# ESQUEMATICO.net
KiCad netlist of a schematic drawn in EasyEDA
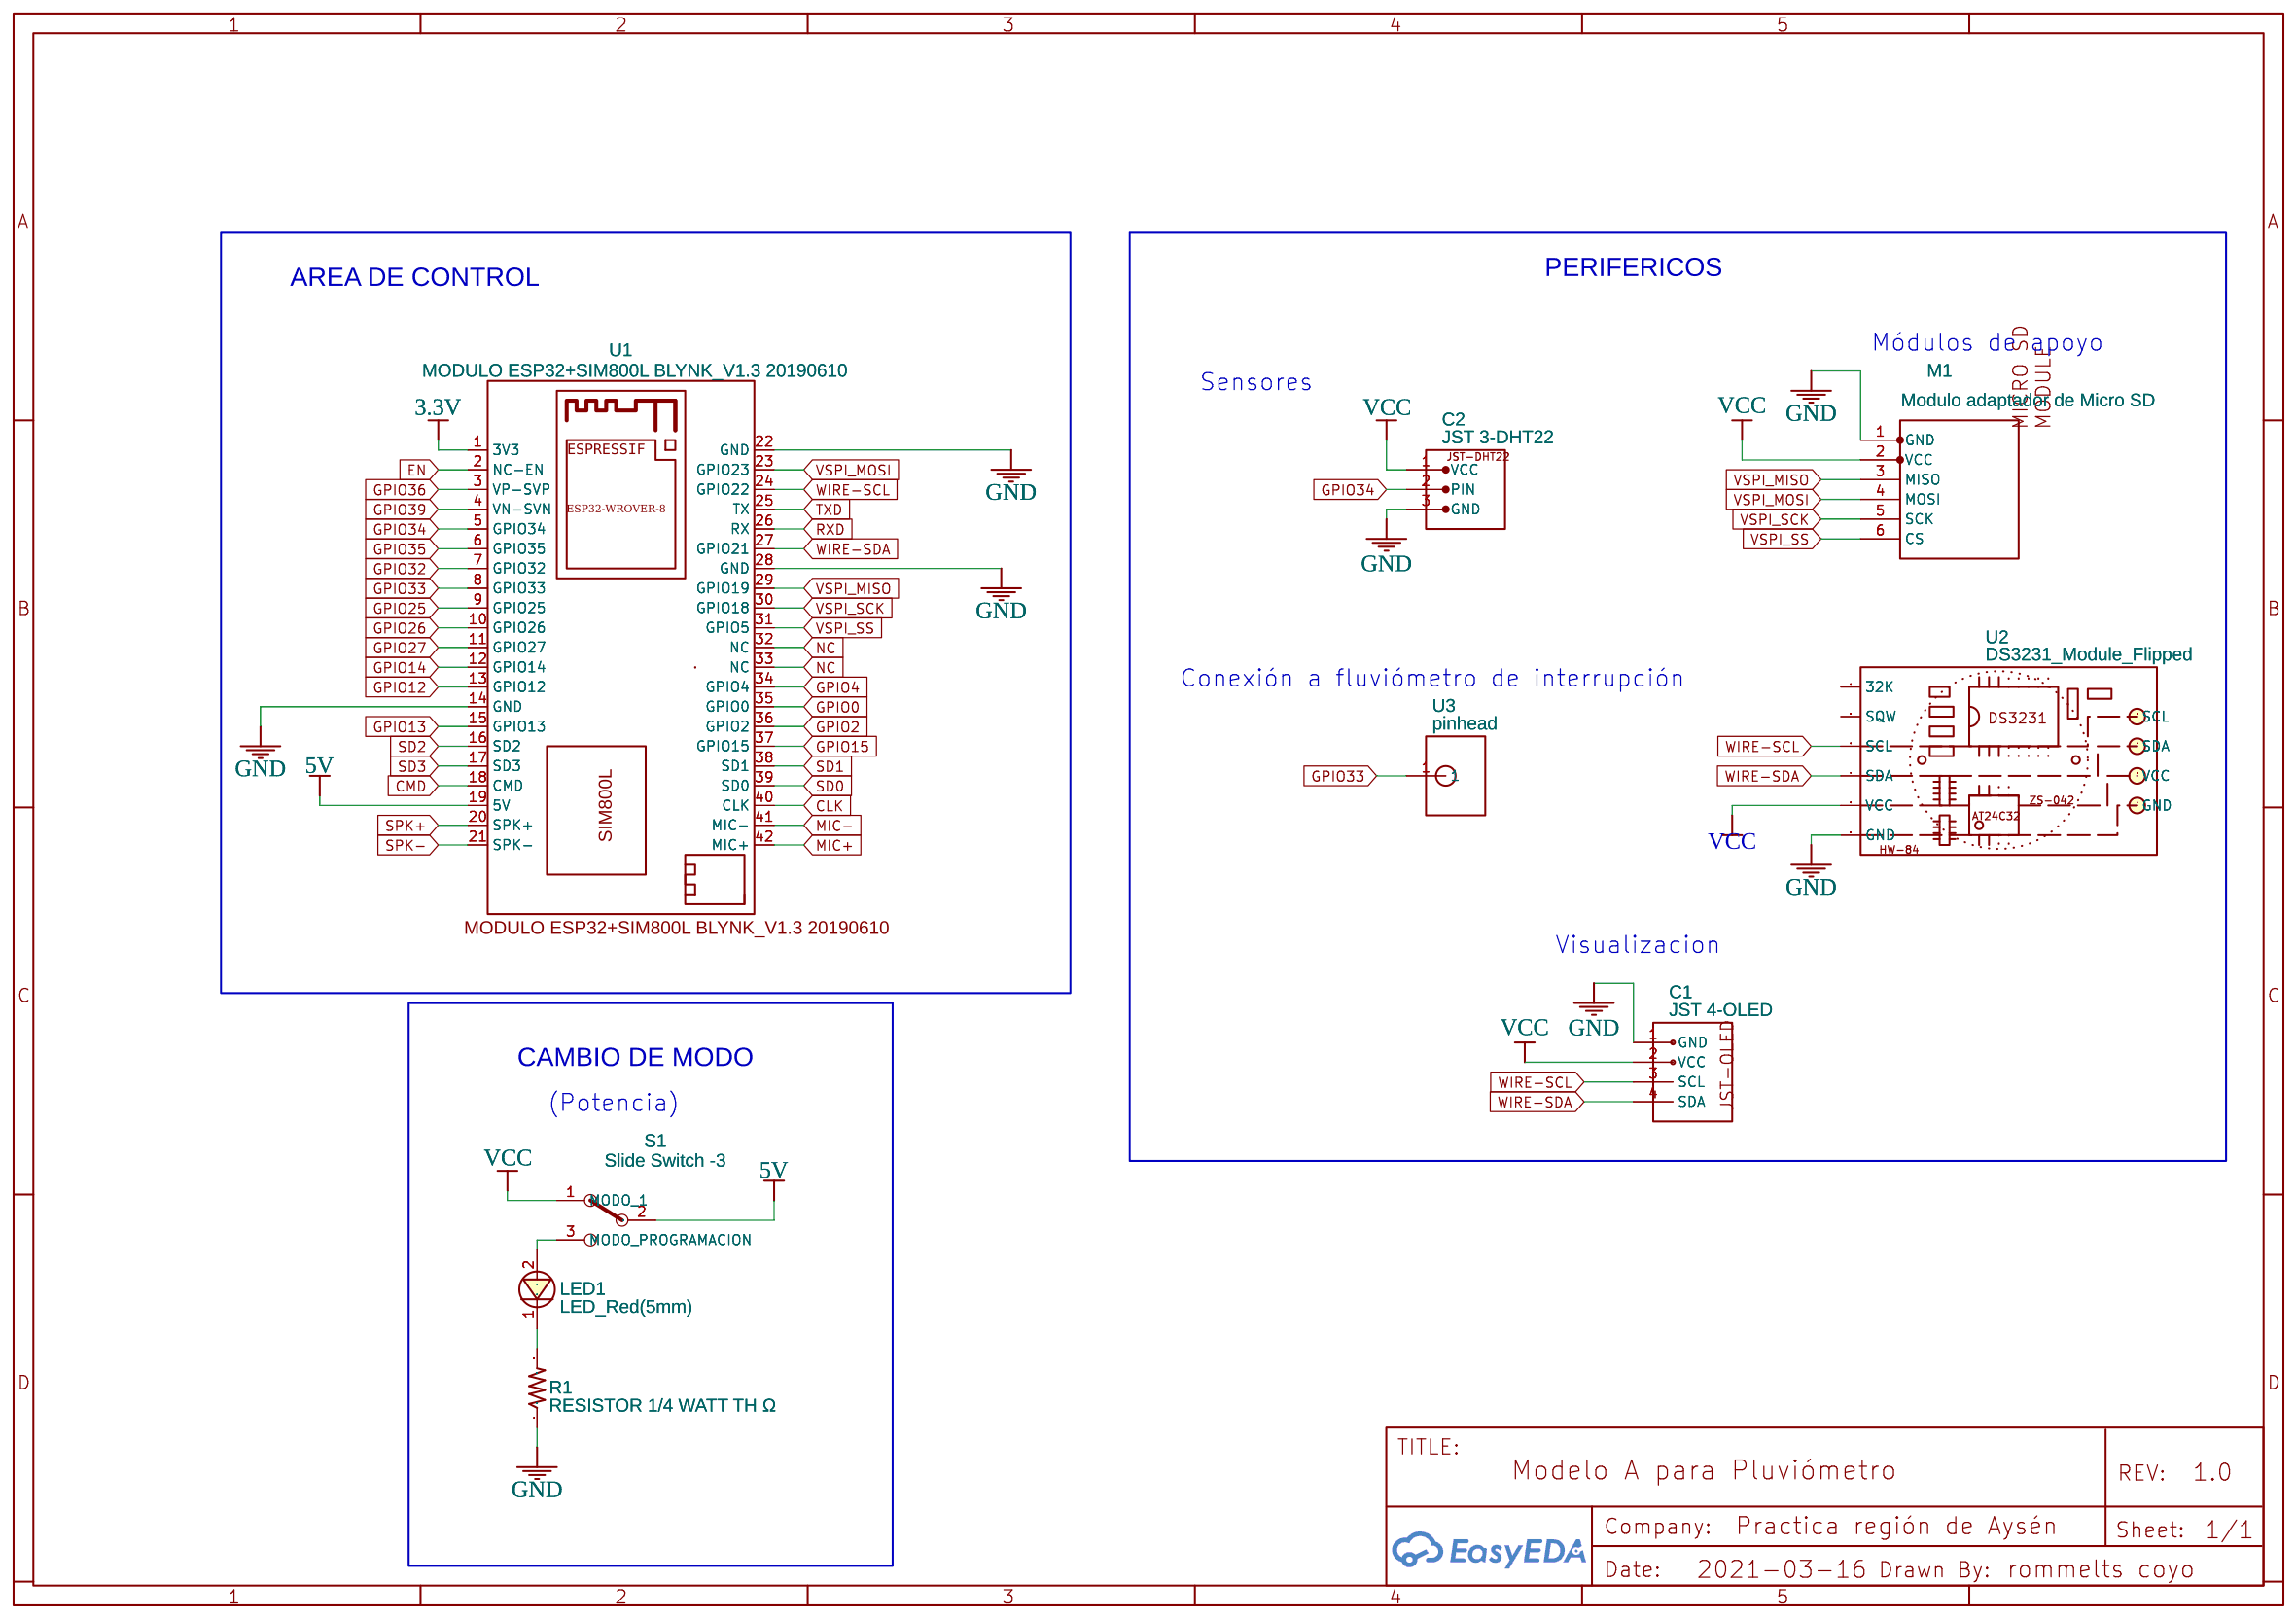
[diagram p0: schematic sheet]

(export (version "E")
  (design (tool "Eeschema 10.0.6"))
  (components
    (comp (ref "C1") (value "JST 4-OLED") (libsource (lib "") (part "JST 4-OLED")))
    (comp (ref "C2") (value "JST 3-DHT22") (libsource (lib "") (part "JST 3-DHT22")))
    (comp (ref "LED1")
      (value "LED_Red(5mm)")
      (fields (field (name "BOM_Manufacturer Part") "LED 5MM"))
      (libsource (lib "") (part "LED_Red(5mm)"))
    )
    (comp (ref "M1")
      (value "Modulo adaptador de Micro SD")
      (libsource (lib "") (part "Modulo adaptador de Micro SD"))
    )
    (comp (ref "R1") (value "RESISTOR 1/4 WATT TH Ω") (libsource (lib "") (part "RESISTOR 1/4 WATT TH Ω")))
    (comp (ref "S1") (value "Slide Switch -3") (libsource (lib "") (part "Slide Switch -3")))
    (comp (ref "U1")
      (value "MODULO ESP32+SIM800L BLYNK_V1.3 20190610")
      (libsource (lib "") (part "MODULO ESP32+SIM800L BLYNK_V1.3 20190610"))
    )
    (comp (ref "U2") (value "DS3231_Module_Flipped") (libsource (lib "") (part "DS3231_Module_Flipped")))
    (comp (ref "U3") (value "pinhead") (libsource (lib "") (part "pinhead")))
  )
  (nets
    (net (code "1") (name "3.3V") (class "Default")
      (node (ref "U1") (pin "1") (pinfunction "3V3_1") (pintype "bidirectional"))
    )
    (net (code "2") (name "5V") (class "Default")
      (node (ref "S1") (pin "2") (pinfunction "NC_2") (pintype "unspecified"))
      (node (ref "U1") (pin "19") (pinfunction "5V_19") (pintype "bidirectional"))
    )
    (net (code "3") (name "CLK") (class "Default")
      (node (ref "U1") (pin "40") (pinfunction "CLK_40") (pintype "unspecified"))
    )
    (net (code "4") (name "CMD") (class "Default")
      (node (ref "U1") (pin "18") (pinfunction "CMD_18") (pintype "unspecified"))
    )
    (net (code "5") (name "EN") (class "Default")
      (node (ref "U1") (pin "2") (pinfunction "NC-EN_2") (pintype "bidirectional"))
    )
    (net (code "6") (name "GND") (class "Default")
      (node (ref "C1") (pin "1") (pinfunction "GND_1") (pintype "unspecified"))
      (node (ref "C2") (pin "3") (pinfunction "GND_3") (pintype "unspecified"))
      (node (ref "M1") (pin "1") (pinfunction "GND_1") (pintype "unspecified"))
      (node (ref "R1") (pin "1") (pinfunction "1_1") (pintype "unspecified"))
      (node (ref "U1") (pin "14") (pinfunction "GND_14") (pintype "bidirectional"))
      (node (ref "U1") (pin "22") (pinfunction "GND_22") (pintype "bidirectional"))
      (node (ref "U1") (pin "28") (pinfunction "GND_28") (pintype "bidirectional"))
      (node (ref "U2") (pin "6") (pinfunction "GND_6") (pintype "unspecified"))
    )
    (net (code "7") (name "GPIO0") (class "Default")
      (node (ref "U1") (pin "35") (pinfunction "GPIO0_35") (pintype "unspecified"))
    )
    (net (code "8") (name "GPIO2") (class "Default")
      (node (ref "U1") (pin "36") (pinfunction "GPIO2_36") (pintype "unspecified"))
    )
    (net (code "9") (name "GPIO4") (class "Default")
      (node (ref "U1") (pin "34") (pinfunction "GPIO4_34") (pintype "unspecified"))
    )
    (net (code "10") (name "GPIO12") (class "Default")
      (node (ref "U1") (pin "13") (pinfunction "GPIO12_13") (pintype "unspecified"))
    )
    (net (code "11") (name "GPIO13") (class "Default")
      (node (ref "U1") (pin "15") (pinfunction "GPIO13_15") (pintype "unspecified"))
    )
    (net (code "12") (name "GPIO14") (class "Default")
      (node (ref "U1") (pin "12") (pinfunction "GPIO14_12") (pintype "unspecified"))
    )
    (net (code "13") (name "GPIO15") (class "Default")
      (node (ref "U1") (pin "37") (pinfunction "GPIO15_37") (pintype "unspecified"))
    )
    (net (code "14") (name "GPIO25") (class "Default")
      (node (ref "U1") (pin "9") (pinfunction "GPIO25_9") (pintype "unspecified"))
    )
    (net (code "15") (name "GPIO26") (class "Default")
      (node (ref "U1") (pin "10") (pinfunction "GPIO26_10") (pintype "unspecified"))
    )
    (net (code "16") (name "GPIO27") (class "Default")
      (node (ref "U1") (pin "11") (pinfunction "GPIO27_11") (pintype "unspecified"))
    )
    (net (code "17") (name "GPIO32") (class "Default")
      (node (ref "U1") (pin "7") (pinfunction "GPIO32_7") (pintype "unspecified"))
    )
    (net (code "18") (name "GPIO33") (class "Default")
      (node (ref "U1") (pin "8") (pinfunction "GPIO33_8") (pintype "unspecified"))
      (node (ref "U3") (pin "1") (pinfunction "1_1") (pintype "unspecified"))
    )
    (net (code "19") (name "GPIO34") (class "Default")
      (node (ref "C2") (pin "2") (pinfunction "PIN_2") (pintype "unspecified"))
      (node (ref "U1") (pin "5") (pinfunction "GPIO34_5") (pintype "unspecified"))
    )
    (net (code "20") (name "GPIO35") (class "Default")
      (node (ref "U1") (pin "6") (pinfunction "GPIO35_6") (pintype "unspecified"))
    )
    (net (code "21") (name "GPIO36") (class "Default")
      (node (ref "U1") (pin "3") (pinfunction "VP-SVP_3") (pintype "unspecified"))
    )
    (net (code "22") (name "GPIO39") (class "Default")
      (node (ref "U1") (pin "4") (pinfunction "VN-SVN_4") (pintype "unspecified"))
    )
    (net (code "23") (name "MIC+") (class "Default")
      (node (ref "U1") (pin "42") (pinfunction "MIC+_42") (pintype "bidirectional"))
    )
    (net (code "24") (name "MIC-") (class "Default")
      (node (ref "U1") (pin "41") (pinfunction "MIC-_41") (pintype "unspecified"))
    )
    (net (code "25") (name "NC") (class "Default")
      (node (ref "U1") (pin "32") (pinfunction "NC_32") (pintype "bidirectional"))
      (node (ref "U1") (pin "33") (pinfunction "NC_33") (pintype "bidirectional"))
    )
    (net (code "26") (name "Net-(LED1-A)") (class "Default")
      (node (ref "LED1") (pin "2") (pinfunction "A_2") (pintype "unspecified"))
      (node (ref "S1") (pin "3") (pinfunction "MODO_PROGRAMACION_3") (pintype "unspecified"))
    )
    (net (code "27") (name "Net-(LED1-K)") (class "Default")
      (node (ref "LED1") (pin "1") (pinfunction "K_1") (pintype "unspecified"))
      (node (ref "R1") (pin "2") (pinfunction "2_2") (pintype "unspecified"))
    )
    (net (code "28") (name "RXD") (class "Default")
      (node (ref "U1") (pin "26") (pinfunction "RX_26") (pintype "unspecified"))
    )
    (net (code "29") (name "SD0") (class "Default")
      (node (ref "U1") (pin "39") (pinfunction "SD0_39") (pintype "unspecified"))
    )
    (net (code "30") (name "SD1") (class "Default")
      (node (ref "U1") (pin "38") (pinfunction "SD1_38") (pintype "unspecified"))
    )
    (net (code "31") (name "SD2") (class "Default")
      (node (ref "U1") (pin "16") (pinfunction "SD2_16") (pintype "unspecified"))
    )
    (net (code "32") (name "SD3") (class "Default")
      (node (ref "U1") (pin "17") (pinfunction "SD3_17") (pintype "unspecified"))
    )
    (net (code "33") (name "SPK+") (class "Default")
      (node (ref "U1") (pin "20") (pinfunction "SPK+_20") (pintype "unspecified"))
    )
    (net (code "34") (name "SPK-") (class "Default")
      (node (ref "U1") (pin "21") (pinfunction "SPK-_21") (pintype "unspecified"))
    )
    (net (code "35") (name "TXD") (class "Default")
      (node (ref "U1") (pin "25") (pinfunction "TX_25") (pintype "unspecified"))
    )
    (net (code "36") (name "VCC") (class "Default")
      (node (ref "C1") (pin "2") (pinfunction "VCC_2") (pintype "unspecified"))
      (node (ref "C2") (pin "1") (pinfunction "VCC_1") (pintype "unspecified"))
      (node (ref "M1") (pin "2") (pinfunction "VCC_2") (pintype "unspecified"))
      (node (ref "S1") (pin "1") (pinfunction "MODO_1_1") (pintype "unspecified"))
      (node (ref "U2") (pin "5") (pinfunction "VCC_5") (pintype "unspecified"))
    )
    (net (code "37") (name "VSPI_MISO") (class "Default")
      (node (ref "M1") (pin "3") (pinfunction "MISO_3") (pintype "unspecified"))
      (node (ref "U1") (pin "29") (pinfunction "GPIO19_29") (pintype "unspecified"))
    )
    (net (code "38") (name "VSPI_MOSI") (class "Default")
      (node (ref "M1") (pin "4") (pinfunction "MOSI_4") (pintype "unspecified"))
      (node (ref "U1") (pin "23") (pinfunction "GPIO23_23") (pintype "unspecified"))
    )
    (net (code "39") (name "VSPI_SCK") (class "Default")
      (node (ref "M1") (pin "5") (pinfunction "SCK_5") (pintype "unspecified"))
      (node (ref "U1") (pin "30") (pinfunction "GPIO18_30") (pintype "unspecified"))
    )
    (net (code "40") (name "VSPI_SS") (class "Default")
      (node (ref "M1") (pin "6") (pinfunction "CS_6") (pintype "unspecified"))
      (node (ref "U1") (pin "31") (pinfunction "GPIO5_31") (pintype "unspecified"))
    )
    (net (code "41") (name "WIRE-SCL") (class "Default")
      (node (ref "C1") (pin "3") (pinfunction "SCL_3") (pintype "unspecified"))
      (node (ref "U1") (pin "24") (pinfunction "GPIO22_24") (pintype "unspecified"))
      (node (ref "U2") (pin "3") (pinfunction "SCL_3") (pintype "unspecified"))
    )
    (net (code "42") (name "WIRE-SDA") (class "Default")
      (node (ref "C1") (pin "4") (pinfunction "SDA_4") (pintype "unspecified"))
      (node (ref "U1") (pin "27") (pinfunction "GPIO21_27") (pintype "unspecified"))
      (node (ref "U2") (pin "4") (pinfunction "SDA_4") (pintype "unspecified"))
    )
    (net (code "43") (name "unconnected-(U2-32K-Pad1)") (class "Default")
      (node (ref "U2") (pin "1") (pinfunction "32K_1") (pintype "unspecified"))
    )
    (net (code "44") (name "unconnected-(U2-GND-Pad7)") (class "Default")
      (node (ref "U2") (pin "7") (pinfunction "GND_7") (pintype "unspecified"))
    )
    (net (code "45") (name "unconnected-(U2-SCL-Pad10)") (class "Default")
      (node (ref "U2") (pin "10") (pinfunction "SCL_10") (pintype "unspecified"))
    )
    (net (code "46") (name "unconnected-(U2-SDA-Pad9)") (class "Default")
      (node (ref "U2") (pin "9") (pinfunction "SDA_9") (pintype "unspecified"))
    )
    (net (code "47") (name "unconnected-(U2-SQW-Pad2)") (class "Default")
      (node (ref "U2") (pin "2") (pinfunction "SQW_2") (pintype "unspecified"))
    )
    (net (code "48") (name "unconnected-(U2-VCC-Pad8)") (class "Default")
      (node (ref "U2") (pin "8") (pinfunction "VCC_8") (pintype "unspecified"))
    )
  )
)
